# Vany-RC-v1_2020-09-15_10-33-21.net
KiCad netlist of a schematic drawn in EasyEDA
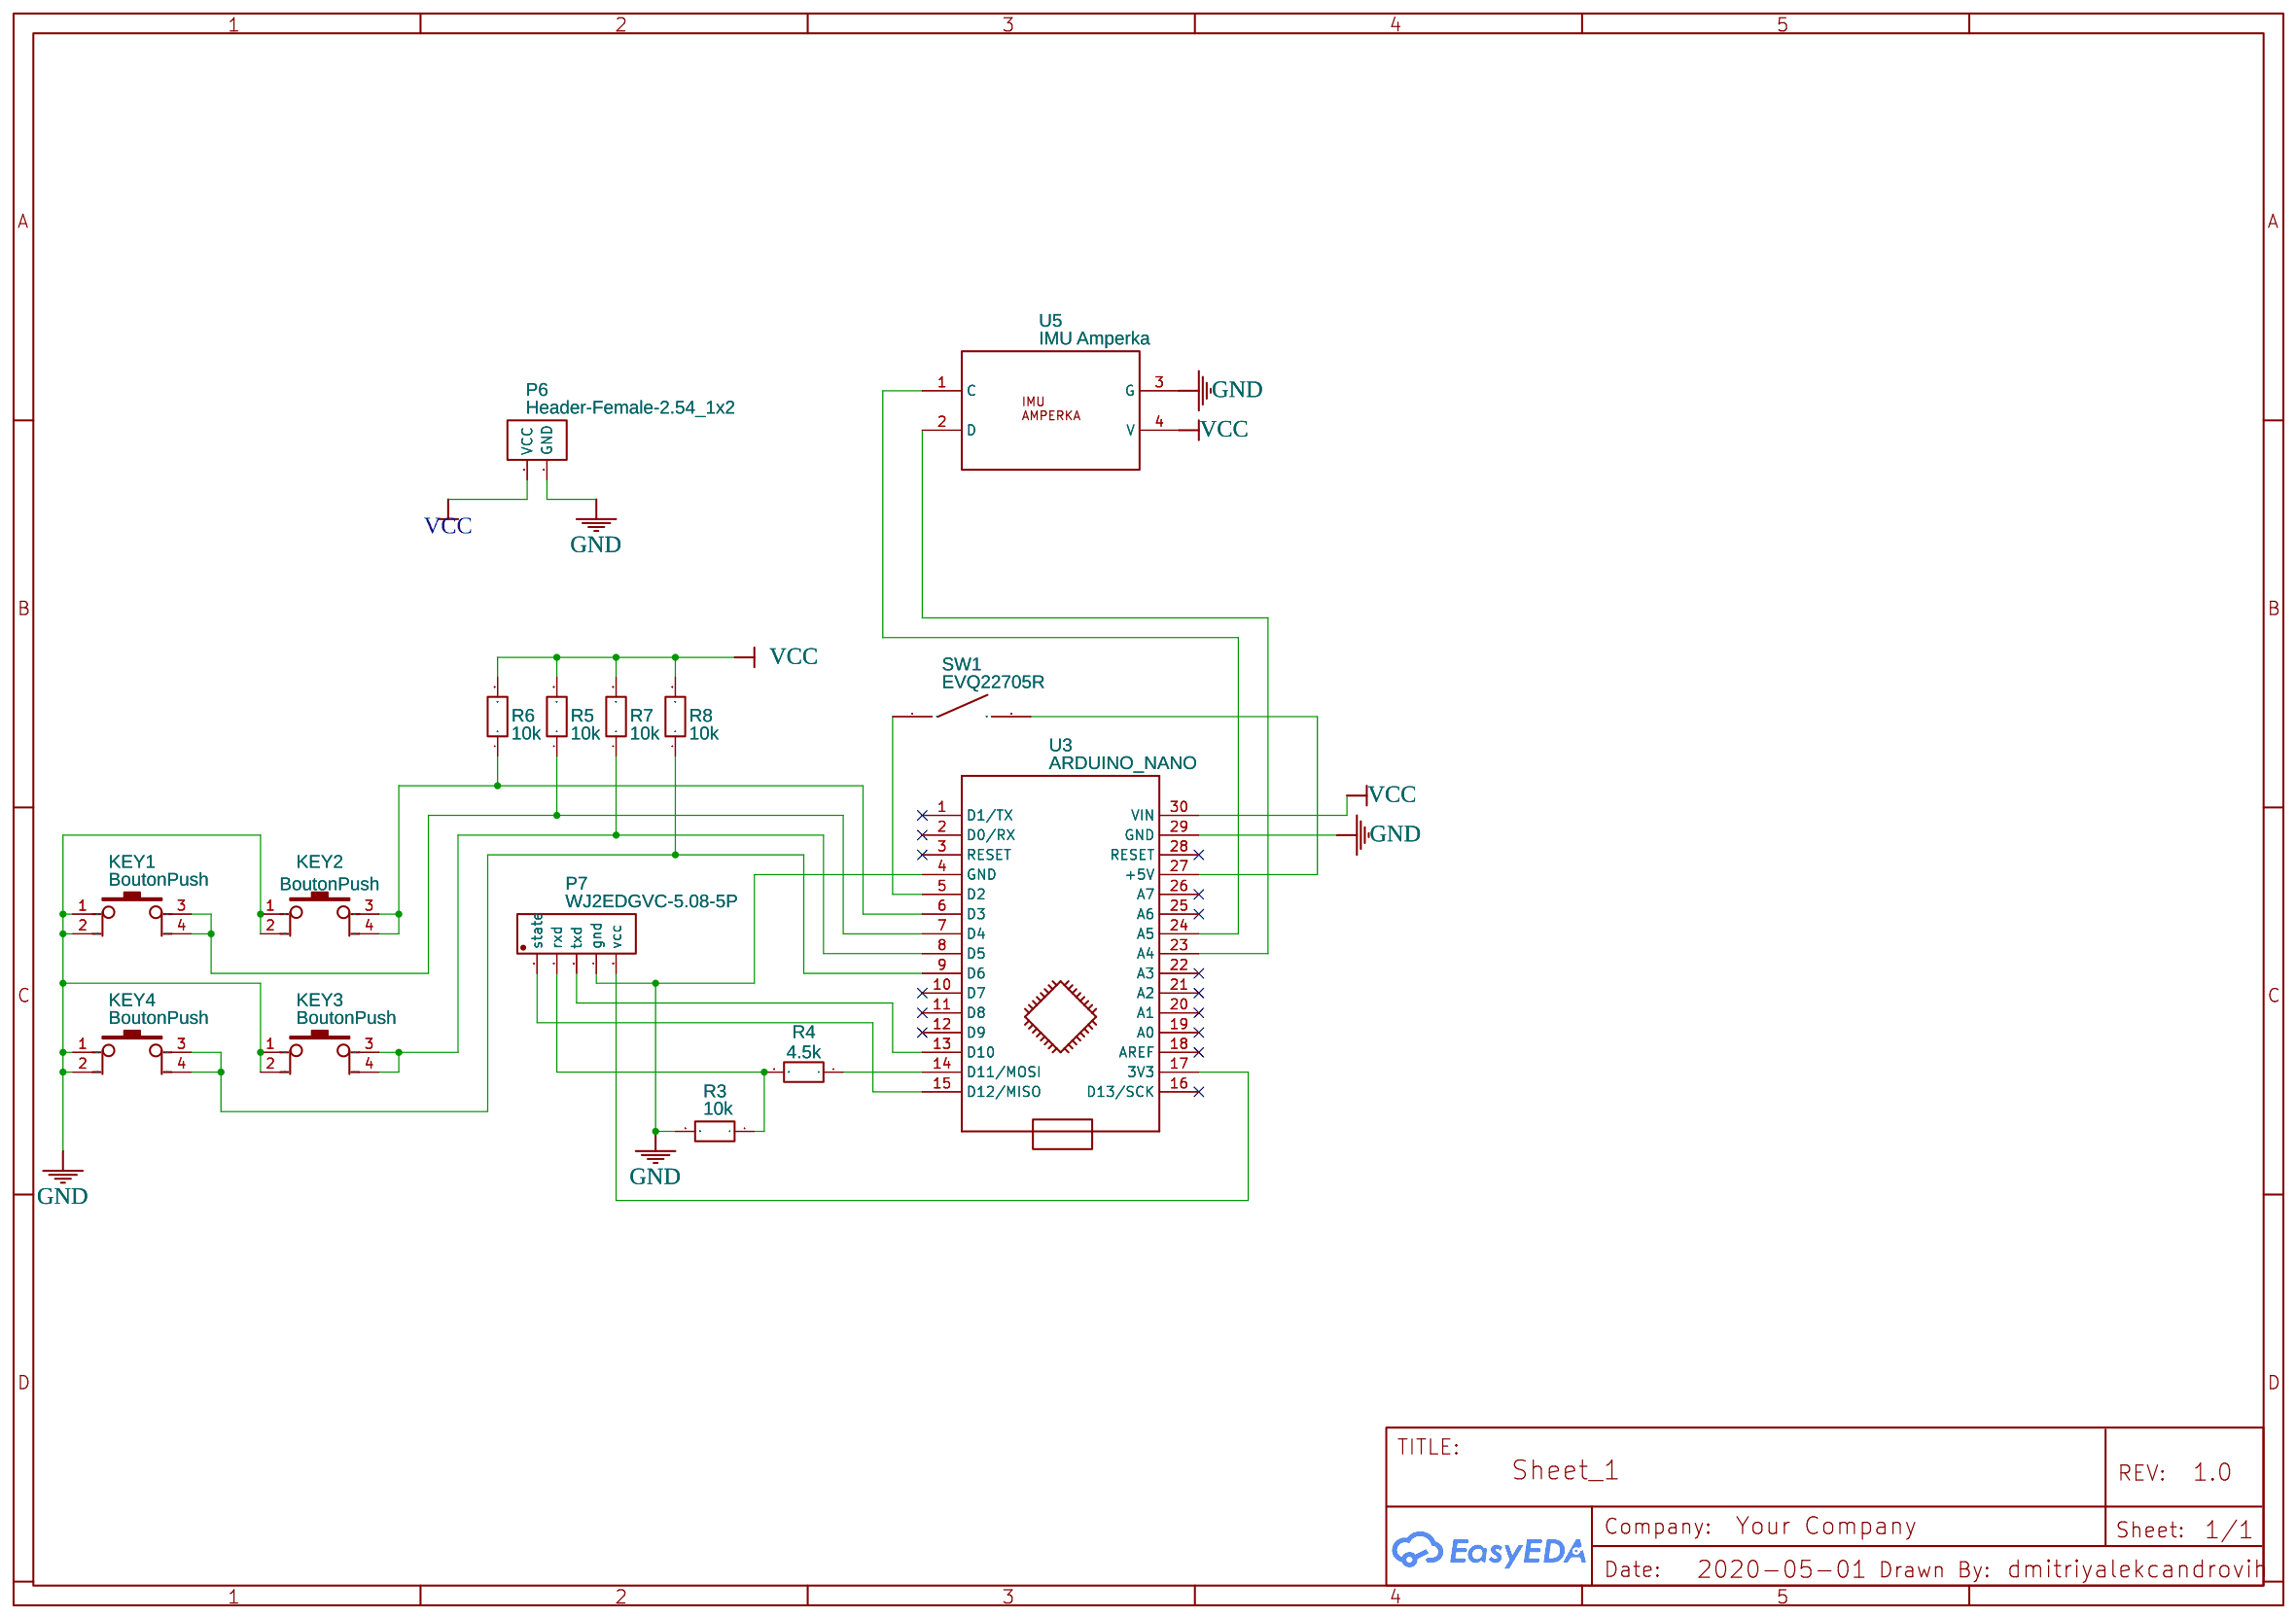
[diagram p0: schematic sheet]

(export (version "E")
  (design (tool "Eeschema 10.0.6"))
  (components
    (comp (ref "KEY1")
      (value "BoutonPush")
      (fields
        (field (name "BOM_Manufacturer Part") "button6*6*8")
        (field (name "BOM_Supplier Part") "C59982")
      )
      (libsource (lib "") (part "BoutonPush"))
    )
    (comp (ref "KEY2")
      (value "BoutonPush")
      (fields
        (field (name "BOM_Manufacturer Part") "button6*6*8")
        (field (name "BOM_Supplier Part") "C59982")
      )
      (libsource (lib "") (part "BoutonPush"))
    )
    (comp (ref "KEY3")
      (value "BoutonPush")
      (fields
        (field (name "BOM_Manufacturer Part") "button6*6*8")
        (field (name "BOM_Supplier Part") "C59982")
      )
      (libsource (lib "") (part "BoutonPush"))
    )
    (comp (ref "KEY4")
      (value "BoutonPush")
      (fields
        (field (name "BOM_Manufacturer Part") "button6*6*8")
        (field (name "BOM_Supplier Part") "C59982")
      )
      (libsource (lib "") (part "BoutonPush"))
    )
    (comp (ref "P6")
      (value "Header-Female-2.54_1x2")
      (fields
        (field (name "BOM_Manufacturer Part") "2.54-1*2PFemale")
        (field (name "BOM_Supplier Part") "C49661")
      )
      (libsource (lib "") (part "Header-Female-2.54_1x2"))
    )
    (comp (ref "P7")
      (value "WJ2EDGVC-5.08-5P")
      (fields (field (name "BOM_Supplier Part") "C8423"))
      (libsource (lib "") (part "WJ2EDGVC-5.08-5P"))
    )
    (comp (ref "R3") (value "10k") (libsource (lib "") (part "Res_AXIAL-0.3(1/8W)_EU_1")))
    (comp (ref "R4") (value "4.5k") (libsource (lib "") (part "Res_AXIAL-0.3(1/8W)_EU_1")))
    (comp (ref "R5") (value "10k") (libsource (lib "") (part "Res_AXIAL-0.3(1/8W)_EU")))
    (comp (ref "R6") (value "10k") (libsource (lib "") (part "Res_AXIAL-0.3(1/8W)_EU")))
    (comp (ref "R7") (value "10k") (libsource (lib "") (part "Res_AXIAL-0.3(1/8W)_EU")))
    (comp (ref "R8") (value "10k") (libsource (lib "") (part "Res_AXIAL-0.3(1/8W)_EU")))
    (comp (ref "SW1")
      (value "EVQ22705R")
      (fields (field (name "BOM_Supplier Part") "C79156"))
      (libsource (lib "") (part "EVQ22705R"))
    )
    (comp (ref "U3") (value "ARDUINO_NANO") (libsource (lib "") (part "ARDUINO_NANO")))
    (comp (ref "U5") (value "IMU Amperka") (libsource (lib "") (part "IMU Amperka")))
  )
  (nets
    (net (code "1") (name "GND") (class "Default")
      (node (ref "KEY1") (pin "1") (pinfunction "1_1") (pintype "input"))
      (node (ref "KEY1") (pin "2") (pinfunction "2_2") (pintype "input"))
      (node (ref "KEY2") (pin "1") (pinfunction "1_1") (pintype "input"))
      (node (ref "KEY2") (pin "2") (pinfunction "2_2") (pintype "input"))
      (node (ref "KEY3") (pin "1") (pinfunction "1_1") (pintype "input"))
      (node (ref "KEY3") (pin "2") (pinfunction "2_2") (pintype "input"))
      (node (ref "KEY4") (pin "1") (pinfunction "1_1") (pintype "input"))
      (node (ref "KEY4") (pin "2") (pinfunction "2_2") (pintype "input"))
      (node (ref "P6") (pin "2") (pinfunction "GND_2") (pintype "passive"))
      (node (ref "P7") (pin "4") (pinfunction "gnd_4") (pintype "passive"))
      (node (ref "R3") (pin "2") (pinfunction "2_2") (pintype "unspecified"))
      (node (ref "U3") (pin "29") (pinfunction "GND_29") (pintype "unspecified"))
      (node (ref "U3") (pin "4") (pinfunction "GND_4") (pintype "unspecified"))
      (node (ref "U5") (pin "3") (pinfunction "G_3") (pintype "unspecified"))
    )
    (net (code "2") (name "Net-(P7-rxd)") (class "Default")
      (node (ref "P7") (pin "2") (pinfunction "rxd_2") (pintype "input"))
      (node (ref "R3") (pin "1") (pinfunction "1_1") (pintype "unspecified"))
      (node (ref "R4") (pin "2") (pinfunction "2_2") (pintype "unspecified"))
    )
    (net (code "3") (name "Net-(P7-state)") (class "Default")
      (node (ref "P7") (pin "1") (pinfunction "state_1") (pintype "output"))
      (node (ref "U3") (pin "15") (pinfunction "D12/MISO_15") (pintype "unspecified"))
    )
    (net (code "4") (name "Net-(P7-txd)") (class "Default")
      (node (ref "P7") (pin "3") (pinfunction "txd_3") (pintype "output"))
      (node (ref "U3") (pin "13") (pinfunction "D10_13") (pintype "unspecified"))
    )
    (net (code "5") (name "Net-(P7-vcc)") (class "Default")
      (node (ref "P7") (pin "5") (pinfunction "vcc_5") (pintype "passive"))
      (node (ref "U3") (pin "17") (pinfunction "3V3_17") (pintype "unspecified"))
    )
    (net (code "6") (name "Net-(U3-+5V)") (class "Default")
      (node (ref "SW1") (pin "2") (pinfunction "2_2") (pintype "input"))
      (node (ref "U3") (pin "27") (pinfunction "+5V_27") (pintype "unspecified"))
    )
    (net (code "7") (name "Net-(U3-A4)") (class "Default")
      (node (ref "U3") (pin "23") (pinfunction "A4_23") (pintype "unspecified"))
      (node (ref "U5") (pin "2") (pinfunction "D_2") (pintype "unspecified"))
    )
    (net (code "8") (name "Net-(U3-A5)") (class "Default")
      (node (ref "U3") (pin "24") (pinfunction "A5_24") (pintype "unspecified"))
      (node (ref "U5") (pin "1") (pinfunction "C_1") (pintype "unspecified"))
    )
    (net (code "9") (name "Net-(U3-D2)") (class "Default")
      (node (ref "SW1") (pin "1") (pinfunction "1_1") (pintype "input"))
      (node (ref "U3") (pin "5") (pinfunction "D2_5") (pintype "unspecified"))
    )
    (net (code "10") (name "Net-(U3-D3)") (class "Default")
      (node (ref "KEY2") (pin "3") (pinfunction "3_3") (pintype "input"))
      (node (ref "KEY2") (pin "4") (pinfunction "4_4") (pintype "input"))
      (node (ref "R6") (pin "1") (pinfunction "1_1") (pintype "unspecified"))
      (node (ref "U3") (pin "6") (pinfunction "D3_6") (pintype "unspecified"))
    )
    (net (code "11") (name "Net-(U3-D4)") (class "Default")
      (node (ref "KEY1") (pin "3") (pinfunction "3_3") (pintype "input"))
      (node (ref "KEY1") (pin "4") (pinfunction "4_4") (pintype "input"))
      (node (ref "R5") (pin "1") (pinfunction "1_1") (pintype "unspecified"))
      (node (ref "U3") (pin "7") (pinfunction "D4_7") (pintype "unspecified"))
    )
    (net (code "12") (name "Net-(U3-D5)") (class "Default")
      (node (ref "KEY3") (pin "3") (pinfunction "3_3") (pintype "input"))
      (node (ref "KEY3") (pin "4") (pinfunction "4_4") (pintype "input"))
      (node (ref "R7") (pin "1") (pinfunction "1_1") (pintype "unspecified"))
      (node (ref "U3") (pin "8") (pinfunction "D5_8") (pintype "unspecified"))
    )
    (net (code "13") (name "Net-(U3-D6)") (class "Default")
      (node (ref "KEY4") (pin "3") (pinfunction "3_3") (pintype "input"))
      (node (ref "KEY4") (pin "4") (pinfunction "4_4") (pintype "input"))
      (node (ref "R8") (pin "1") (pinfunction "1_1") (pintype "unspecified"))
      (node (ref "U3") (pin "9") (pinfunction "D6_9") (pintype "unspecified"))
    )
    (net (code "14") (name "Net-(U3-D11{slash}MOSI)") (class "Default")
      (node (ref "R4") (pin "1") (pinfunction "1_1") (pintype "unspecified"))
      (node (ref "U3") (pin "14") (pinfunction "D11/MOSI_14") (pintype "unspecified"))
    )
    (net (code "15") (name "VCC") (class "Default")
      (node (ref "P6") (pin "1") (pinfunction "VCC_1") (pintype "passive"))
      (node (ref "R5") (pin "2") (pinfunction "2_2") (pintype "unspecified"))
      (node (ref "R6") (pin "2") (pinfunction "2_2") (pintype "unspecified"))
      (node (ref "R7") (pin "2") (pinfunction "2_2") (pintype "unspecified"))
      (node (ref "R8") (pin "2") (pinfunction "2_2") (pintype "unspecified"))
      (node (ref "U3") (pin "30") (pinfunction "VIN_30") (pintype "unspecified"))
      (node (ref "U5") (pin "4") (pinfunction "V_4") (pintype "unspecified"))
    )
    (net (code "16") (name "unconnected-(U3-A0-Pad19)") (class "Default")
      (node (ref "U3") (pin "19") (pinfunction "A0_19") (pintype "unspecified+no_connect"))
    )
    (net (code "17") (name "unconnected-(U3-A1-Pad20)") (class "Default")
      (node (ref "U3") (pin "20") (pinfunction "A1_20") (pintype "unspecified+no_connect"))
    )
    (net (code "18") (name "unconnected-(U3-A2-Pad21)") (class "Default")
      (node (ref "U3") (pin "21") (pinfunction "A2_21") (pintype "unspecified+no_connect"))
    )
    (net (code "19") (name "unconnected-(U3-A3-Pad22)") (class "Default")
      (node (ref "U3") (pin "22") (pinfunction "A3_22") (pintype "unspecified+no_connect"))
    )
    (net (code "20") (name "unconnected-(U3-A6-Pad25)") (class "Default")
      (node (ref "U3") (pin "25") (pinfunction "A6_25") (pintype "unspecified+no_connect"))
    )
    (net (code "21") (name "unconnected-(U3-A7-Pad26)") (class "Default")
      (node (ref "U3") (pin "26") (pinfunction "A7_26") (pintype "unspecified+no_connect"))
    )
    (net (code "22") (name "unconnected-(U3-AREF-Pad18)") (class "Default")
      (node (ref "U3") (pin "18") (pinfunction "AREF_18") (pintype "unspecified+no_connect"))
    )
    (net (code "23") (name "unconnected-(U3-D0{slash}RX-Pad2)") (class "Default")
      (node (ref "U3") (pin "2") (pinfunction "D0/RX_2") (pintype "unspecified+no_connect"))
    )
    (net (code "24") (name "unconnected-(U3-D1{slash}TX-Pad1)") (class "Default")
      (node (ref "U3") (pin "1") (pinfunction "D1/TX_1") (pintype "unspecified+no_connect"))
    )
    (net (code "25") (name "unconnected-(U3-D7-Pad10)") (class "Default")
      (node (ref "U3") (pin "10") (pinfunction "D7_10") (pintype "unspecified+no_connect"))
    )
    (net (code "26") (name "unconnected-(U3-D8-Pad11)") (class "Default")
      (node (ref "U3") (pin "11") (pinfunction "D8_11") (pintype "unspecified+no_connect"))
    )
    (net (code "27") (name "unconnected-(U3-D9-Pad12)") (class "Default")
      (node (ref "U3") (pin "12") (pinfunction "D9_12") (pintype "unspecified+no_connect"))
    )
    (net (code "28") (name "unconnected-(U3-D13{slash}SCK-Pad16)") (class "Default")
      (node (ref "U3") (pin "16") (pinfunction "D13/SCK_16") (pintype "unspecified+no_connect"))
    )
    (net (code "29") (name "unconnected-(U3-RESET-Pad3)") (class "Default")
      (node (ref "U3") (pin "3") (pinfunction "RESET_3") (pintype "unspecified+no_connect"))
    )
    (net (code "30") (name "unconnected-(U3-RESET-Pad28)") (class "Default")
      (node (ref "U3") (pin "28") (pinfunction "RESET_28") (pintype "unspecified+no_connect"))
    )
  )
)
